# Audio.net
KiCad netlist of a schematic drawn in Altium Designer
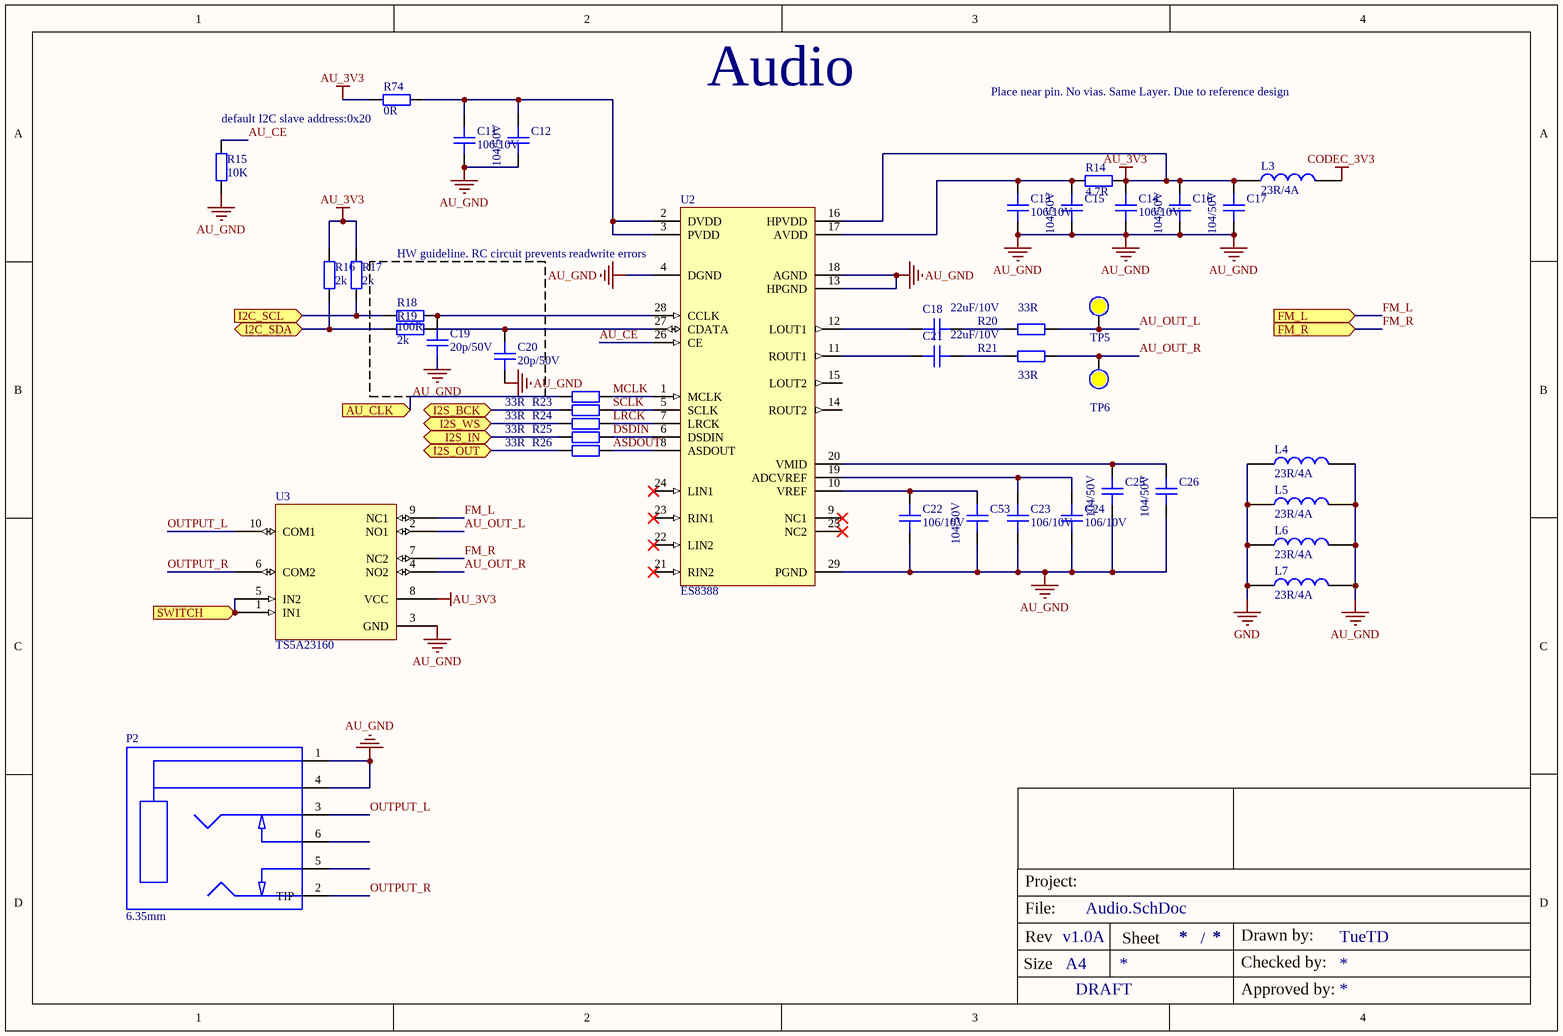
[diagram p0: Audio.SchDoc]

(export (version "E")
  (design (tool "Eeschema 10.0.6"))
  (components
    (comp (ref "C11")
      (value "106/10V")
      (footprint "CAPC-0603 (1608)")
      (description "CAP CER 10uF 10% 10V X5R 0603")
      (fields (field (name "MPN") "CL10A106KP8NNNC"))
      (libsource (lib "lib") (part "CL10A106KP8NNNC"))
    )
    (comp (ref "C12")
      (value "104/50V")
      (footprint "CAPC-0603 (1608)")
      (description "CAP CER 0.1uF 50V 10% X7R 0603")
      (fields (field (name "MPN") "C0603C104K5RACTU"))
      (libsource (lib "lib") (part "C0603C104K5RACTU"))
    )
    (comp (ref "C13")
      (value "106/10V")
      (footprint "CAPC-0603 (1608)")
      (description "CAP CER 10uF 10% 10V X5R 0603")
      (fields (field (name "MPN") "CL10A106KP8NNNC"))
      (libsource (lib "lib") (part "CL10A106KP8NNNC"))
    )
    (comp (ref "C14")
      (value "106/10V")
      (footprint "CAPC-0603 (1608)")
      (description "CAP CER 10uF 10% 10V X5R 0603")
      (fields (field (name "MPN") "CL10A106KP8NNNC"))
      (libsource (lib "lib") (part "CL10A106KP8NNNC"))
    )
    (comp (ref "C15")
      (value "104/50V")
      (footprint "CAPC-0603 (1608)")
      (description "CAP CER 0.1uF 50V 10% X7R 0603")
      (fields (field (name "MPN") "C0603C104K5RACTU"))
      (libsource (lib "lib") (part "C0603C104K5RACTU"))
    )
    (comp (ref "C16")
      (value "104/50V")
      (footprint "CAPC-0603 (1608)")
      (description "CAP CER 0.1uF 50V 10% X7R 0603")
      (fields (field (name "MPN") "C0603C104K5RACTU"))
      (libsource (lib "lib") (part "C0603C104K5RACTU"))
    )
    (comp (ref "C17")
      (value "104/50V")
      (footprint "CAPC-0603 (1608)")
      (description "CAP CER 0.1uF 50V 10% X7R 0603")
      (fields (field (name "MPN") "C0603C104K5RACTU"))
      (libsource (lib "lib") (part "C0603C104K5RACTU"))
    )
    (comp (ref "C18")
      (value "22uF/10V")
      (footprint "CAPC-0603 (1608)")
      (description "CAP CER 22UF 10V X5R 0603")
      (fields (field (name "MPN") "CL10A226MPCNUBE"))
      (libsource (lib "lib") (part "CL10A226MPCNUBE"))
    )
    (comp (ref "C19")
      (value "20p/50V")
      (footprint "CAPC-0603 (1608)")
      (description "CAP CER 20pF 5% 50V C0G/NP0 0603")
      (fields (field (name "MPN") "CL10C200JB8NNNC"))
      (libsource (lib "lib") (part "CL10C200JB8NNNC"))
    )
    (comp (ref "C20")
      (value "20p/50V")
      (footprint "CAPC-0603 (1608)")
      (description "CAP CER 20pF 5% 50V C0G/NP0 0603")
      (fields (field (name "MPN") "CL10C200JB8NNNC"))
      (libsource (lib "lib") (part "CL10C200JB8NNNC"))
    )
    (comp (ref "C21")
      (value "22uF/10V")
      (footprint "CAPC-0603 (1608)")
      (description "CAP CER 22UF 10V X5R 0603")
      (fields (field (name "MPN") "CL10A226MPCNUBE"))
      (libsource (lib "lib") (part "CL10A226MPCNUBE"))
    )
    (comp (ref "C22")
      (value "106/10V")
      (footprint "CAPC-0603 (1608)")
      (description "CAP CER 10uF 10% 10V X5R 0603")
      (fields (field (name "MPN") "CL10A106KP8NNNC"))
      (libsource (lib "lib") (part "CL10A106KP8NNNC"))
    )
    (comp (ref "C23")
      (value "106/10V")
      (footprint "CAPC-0603 (1608)")
      (description "CAP CER 10uF 10% 10V X5R 0603")
      (fields (field (name "MPN") "CL10A106KP8NNNC"))
      (libsource (lib "lib") (part "CL10A106KP8NNNC"))
    )
    (comp (ref "C24")
      (value "106/10V")
      (footprint "CAPC-0603 (1608)")
      (description "CAP CER 10uF 10% 10V X5R 0603")
      (fields (field (name "MPN") "CL10A106KP8NNNC"))
      (libsource (lib "lib") (part "CL10A106KP8NNNC"))
    )
    (comp (ref "C25")
      (value "104/50V")
      (footprint "CAPC-0603 (1608)")
      (description "CAP CER 0.1uF 50V 10% X7R 0603")
      (fields (field (name "MPN") "C0603C104K5RACTU"))
      (libsource (lib "lib") (part "C0603C104K5RACTU"))
    )
    (comp (ref "C26")
      (value "104/50V")
      (footprint "CAPC-0603 (1608)")
      (description "CAP CER 0.1uF 50V 10% X7R 0603")
      (fields (field (name "MPN") "C0603C104K5RACTU"))
      (libsource (lib "lib") (part "C0603C104K5RACTU"))
    )
    (comp (ref "C53")
      (value "104/50V")
      (footprint "CAPC-0603 (1608)")
      (description "CAP CER 0.1uF 50V 10% X7R 0603")
      (fields (field (name "MPN") "C0603C104K5RACTU"))
      (libsource (lib "lib") (part "C0603C104K5RACTU"))
    )
    (comp (ref "L3")
      (value "23R/4A")
      (footprint "IND-0603 (1608)")
      (description "IND-FERRITE BEAD 23 OHM  4A 0603 1LN")
      (fields (field (name "MPN") "FBMJ1608HM230NT"))
      (libsource (lib "lib") (part "FBMJ1608HM230NT"))
    )
    (comp (ref "L4")
      (value "23R/4A")
      (footprint "IND-0603 (1608)")
      (description "IND-FERRITE BEAD 23 OHM  4A 0603 1LN")
      (fields (field (name "MPN") "FBMJ1608HM230NT"))
      (libsource (lib "01.Passives") (part "FBMJ1608HM230NT"))
    )
    (comp (ref "L5")
      (value "23R/4A")
      (footprint "IND-0603 (1608)")
      (description "IND-FERRITE BEAD 23 OHM  4A 0603 1LN")
      (fields (field (name "MPN") "FBMJ1608HM230NT"))
      (libsource (lib "01.Passives") (part "FBMJ1608HM230NT"))
    )
    (comp (ref "L6")
      (value "23R/4A")
      (footprint "IND-0603 (1608)")
      (description "IND-FERRITE BEAD 23 OHM  4A 0603 1LN")
      (fields (field (name "MPN") "FBMJ1608HM230NT"))
      (libsource (lib "01.Passives") (part "FBMJ1608HM230NT"))
    )
    (comp (ref "L7")
      (value "23R/4A")
      (footprint "IND-0603 (1608)")
      (description "IND-FERRITE BEAD 23 OHM  4A 0603 1LN")
      (fields (field (name "MPN") "FBMJ1608HM230NT"))
      (libsource (lib "01.Passives") (part "FBMJ1608HM230NT"))
    )
    (comp (ref "P2")
      (value "6.35mm")
      (footprint "CK-6.35-636A")
      (description "CONN JACK STEREO 1/4\" R/A")
      (fields
        (field (name "MFR") "DONGGUAN YIJIAN ELECTRONICS CO., LTD.")
        (field (name "MPN") "CK-6.35-636A")
      )
      (libsource (lib "lib") (part "CK-6.35-636A"))
    )
    (comp (ref "R14")
      (value "4.7R")
      (footprint "RESC-0603 (1608)")
      (description "RES SMD 4.7 OHM 1% 1/10W 0603")
      (fields (field (name "MPN") "RC0603FR-074R7L"))
      (libsource (lib "lib") (part "RC0603FR-074R7L"))
    )
    (comp (ref "R15")
      (value "10K")
      (footprint "RESC-0603 (1608)")
      (description "RES SMD 10K OHM 1% 1/10W 0603")
      (fields (field (name "MPN") "RC0603FR-0710KL"))
      (libsource (lib "lib") (part "RC0603FR-0710KL"))
    )
    (comp (ref "R16")
      (value "2k")
      (footprint "RESC-0603 (1608)")
      (description "RES SMD 2 KOHM 1% 1/10W 0603")
      (fields (field (name "MPN") "RC0603FR-072KL"))
      (libsource (lib "lib") (part "RC0603FR-072KL"))
    )
    (comp (ref "R17")
      (value "2k")
      (footprint "RESC-0603 (1608)")
      (description "RES SMD 2 KOHM 1% 1/10W 0603")
      (fields (field (name "MPN") "RC0603FR-072KL"))
      (libsource (lib "lib") (part "RC0603FR-072KL"))
    )
    (comp (ref "R18")
      (value "100R")
      (footprint "RESC-0603 (1608)")
      (description "RES SMD 100 OHM 1% 1/10W 0603")
      (fields (field (name "MPN") "RC0603FR-07100RL"))
      (libsource (lib "lib") (part "RC0603FR-07100RL"))
    )
    (comp (ref "R19")
      (value "2k")
      (footprint "RESC-0603 (1608)")
      (description "RES SMD 2 KOHM 1% 1/10W 0603")
      (fields (field (name "MPN") "RC0603FR-072KL"))
      (libsource (lib "") (part "RC0603FR-072KL_1"))
    )
    (comp (ref "R20")
      (value "33R")
      (footprint "RESC-0603 (1608)")
      (description "RES SMD 33 OHM 1% 1/10W 0603")
      (fields (field (name "MPN") "RC0603FR-0733RL") (field (name "MFR") "Yageo"))
      (libsource (lib "lib") (part "RC0603FR-0733RL"))
    )
    (comp (ref "R21")
      (value "33R")
      (footprint "RESC-0603 (1608)")
      (description "RES SMD 33 OHM 1% 1/10W 0603")
      (fields (field (name "MPN") "RC0603FR-0733RL") (field (name "MFR") "Yageo"))
      (libsource (lib "lib") (part "RC0603FR-0733RL"))
    )
    (comp (ref "R22")
      (value "33R")
      (footprint "RESC-0603 (1608)")
      (description "RES SMD 33 OHM 1% 1/10W 0603")
      (fields (field (name "MPN") "RC0603FR-0733RL") (field (name "MFR") "Yageo"))
      (libsource (lib "lib") (part "RC0603FR-0733RL"))
    )
    (comp (ref "R23")
      (value "33R")
      (footprint "RESC-0603 (1608)")
      (description "RES SMD 33 OHM 1% 1/10W 0603")
      (fields (field (name "MPN") "RC0603FR-0733RL") (field (name "MFR") "Yageo"))
      (libsource (lib "lib") (part "RC0603FR-0733RL"))
    )
    (comp (ref "R24")
      (value "33R")
      (footprint "RESC-0603 (1608)")
      (description "RES SMD 33 OHM 1% 1/10W 0603")
      (fields (field (name "MPN") "RC0603FR-0733RL") (field (name "MFR") "Yageo"))
      (libsource (lib "lib") (part "RC0603FR-0733RL"))
    )
    (comp (ref "R25")
      (value "33R")
      (footprint "RESC-0603 (1608)")
      (description "RES SMD 33 OHM 1% 1/10W 0603")
      (fields (field (name "MPN") "RC0603FR-0733RL") (field (name "MFR") "Yageo"))
      (libsource (lib "lib") (part "RC0603FR-0733RL"))
    )
    (comp (ref "R26")
      (value "33R")
      (footprint "RESC-0603 (1608)")
      (description "RES SMD 33 OHM 1% 1/10W 0603")
      (fields (field (name "MPN") "RC0603FR-0733RL") (field (name "MFR") "Yageo"))
      (libsource (lib "lib") (part "RC0603FR-0733RL"))
    )
    (comp (ref "R74")
      (value "0R")
      (footprint "RESC-0603 (1608)")
      (description "RES SMD 0.0OHM JUMPER 1/10W 0603")
      (fields (field (name "MPN") "RC0603FR-070RL"))
      (libsource (lib "lib") (part "RC0603FR-070RL"))
    )
    (comp (ref "TP5")
      (value "~")
      (footprint "Test Point 1.5 MM")
      (description "Test Point")
      (libsource (lib "lib") (part "Test Point"))
    )
    (comp (ref "TP6")
      (value "~")
      (footprint "Test Point 1.5 MM")
      (description "Test Point")
      (libsource (lib "") (part "Test Point_1"))
    )
    (comp (ref "U2")
      (value "ES8388")
      (footprint "QFN28 - ES8388")
      (description "The Audio Codec Chip, is a low power stereo audio codec")
      (fields (field (name "MFR") "Everest-Semi"))
      (libsource (lib "lib") (part "ES8388"))
    )
    (comp (ref "U3")
      (value "TS5A23160")
      (footprint "TSSOP50P490X110-10N")
      (description "IC SWITCH SPDT DUAL 10VSSOP")
      (fields (field (name "MPN") "TS5A23160DGSR") (field (name "MFR") "Texas Instruments"))
      (libsource (lib "lib") (part "TS5A23160DGSR"))
    )
  )
  (nets
    (net (code "1") (name "/ASDOUT") (class "Default")
      (node (ref "R26") (pin "2") (pinfunction "2_2") (pintype "passive"))
      (node (ref "U2") (pin "8") (pinfunction "ASDOUT_8") (pintype "passive"))
    )
    (net (code "2") (name "/AU_CE") (class "Default")
      (node (ref "R15") (pin "2") (pinfunction "2_2") (pintype "passive"))
      (node (ref "U2") (pin "26") (pinfunction "CE_26") (pintype "input"))
    )
    (net (code "3") (name "/AU_CLK") (class "Default")
      (node (ref "R22") (pin "1") (pinfunction "1_1") (pintype "passive"))
    )
    (net (code "4") (name "/AU_OUT_L") (class "Default")
      (node (ref "R20") (pin "2") (pinfunction "2_2") (pintype "passive"))
      (node (ref "TP5") (pin "0") (pinfunction "0_0") (pintype "passive"))
      (node (ref "U3") (pin "2") (pinfunction "NO1_2") (pintype "bidirectional"))
    )
    (net (code "5") (name "/AU_OUT_R") (class "Default")
      (node (ref "R21") (pin "2") (pinfunction "2_2") (pintype "passive"))
      (node (ref "TP6") (pin "0") (pinfunction "0_0") (pintype "passive"))
      (node (ref "U3") (pin "4") (pinfunction "NO2_4") (pintype "bidirectional"))
    )
    (net (code "6") (name "/DSDIN") (class "Default")
      (node (ref "R25") (pin "2") (pinfunction "2_2") (pintype "passive"))
      (node (ref "U2") (pin "6") (pinfunction "DSDIN_6") (pintype "passive"))
    )
    (net (code "7") (name "/FM_L") (class "Default")
      (node (ref "U3") (pin "9") (pinfunction "NC1_9") (pintype "bidirectional"))
    )
    (net (code "8") (name "/FM_R") (class "Default")
      (node (ref "U3") (pin "7") (pinfunction "NC2_7") (pintype "bidirectional"))
    )
    (net (code "9") (name "/I2C_SCL") (class "Default")
      (node (ref "R17") (pin "1") (pinfunction "1_1") (pintype "passive"))
      (node (ref "R18") (pin "1") (pinfunction "1_1") (pintype "passive"))
    )
    (net (code "10") (name "/I2C_SDA") (class "Default")
      (node (ref "R16") (pin "1") (pinfunction "1_1") (pintype "passive"))
      (node (ref "R19") (pin "1") (pinfunction "1_1") (pintype "passive"))
    )
    (net (code "11") (name "/I2S_BCK") (class "Default")
      (node (ref "R23") (pin "1") (pinfunction "1_1") (pintype "passive"))
    )
    (net (code "12") (name "/I2S_IN") (class "Default")
      (node (ref "R25") (pin "1") (pinfunction "1_1") (pintype "passive"))
    )
    (net (code "13") (name "/I2S_OUT") (class "Default")
      (node (ref "R26") (pin "1") (pinfunction "1_1") (pintype "passive"))
    )
    (net (code "14") (name "/I2S_WS") (class "Default")
      (node (ref "R24") (pin "1") (pinfunction "1_1") (pintype "passive"))
    )
    (net (code "15") (name "/LRCK") (class "Default")
      (node (ref "R24") (pin "2") (pinfunction "2_2") (pintype "passive"))
      (node (ref "U2") (pin "7") (pinfunction "LRCK_7") (pintype "passive"))
    )
    (net (code "16") (name "/MCLK") (class "Default")
      (node (ref "R22") (pin "2") (pinfunction "2_2") (pintype "passive"))
      (node (ref "U2") (pin "1") (pinfunction "MCLK_1") (pintype "input"))
    )
    (net (code "17") (name "/OUTPUT_L") (class "Default")
      (node (ref "P2") (pin "3") (pinfunction "RING_3") (pintype "passive"))
      (node (ref "U3") (pin "10") (pinfunction "COM1_10") (pintype "bidirectional"))
    )
    (net (code "18") (name "/OUTPUT_R") (class "Default")
      (node (ref "P2") (pin "2") (pinfunction "TIP_2") (pintype "passive"))
      (node (ref "U3") (pin "6") (pinfunction "COM2_6") (pintype "bidirectional"))
    )
    (net (code "19") (name "/SCLK") (class "Default")
      (node (ref "R23") (pin "2") (pinfunction "2_2") (pintype "passive"))
      (node (ref "U2") (pin "5") (pinfunction "SCLK_5") (pintype "passive"))
    )
    (net (code "20") (name "/SWITCH") (class "Default")
      (node (ref "U3") (pin "1") (pinfunction "IN1_1") (pintype "input"))
      (node (ref "U3") (pin "5") (pinfunction "IN2_5") (pintype "input"))
    )
    (net (code "21") (name "AU_3V3") (class "Default")
      (node (ref "C14") (pin "2") (pinfunction "2_2") (pintype "passive"))
      (node (ref "C16") (pin "2") (pinfunction "2_2") (pintype "passive"))
      (node (ref "C17") (pin "2") (pinfunction "2_2") (pintype "passive"))
      (node (ref "L3") (pin "1") (pinfunction "1_1") (pintype "passive"))
      (node (ref "R14") (pin "2") (pinfunction "2_2") (pintype "passive"))
      (node (ref "R16") (pin "2") (pinfunction "2_2") (pintype "passive"))
      (node (ref "R17") (pin "2") (pinfunction "2_2") (pintype "passive"))
      (node (ref "R74") (pin "1") (pinfunction "1_1") (pintype "passive"))
      (node (ref "U2") (pin "16") (pinfunction "HPVDD_16") (pintype "power_in"))
      (node (ref "U3") (pin "8") (pinfunction "VCC_8") (pintype "power_in"))
    )
    (net (code "22") (name "AU_GND") (class "Default")
      (node (ref "C11") (pin "1") (pinfunction "1_1") (pintype "passive"))
      (node (ref "C12") (pin "1") (pinfunction "1_1") (pintype "passive"))
      (node (ref "C13") (pin "1") (pinfunction "1_1") (pintype "passive"))
      (node (ref "C14") (pin "1") (pinfunction "1_1") (pintype "passive"))
      (node (ref "C15") (pin "1") (pinfunction "1_1") (pintype "passive"))
      (node (ref "C16") (pin "1") (pinfunction "1_1") (pintype "passive"))
      (node (ref "C17") (pin "1") (pinfunction "1_1") (pintype "passive"))
      (node (ref "C19") (pin "1") (pinfunction "1_1") (pintype "passive"))
      (node (ref "C20") (pin "1") (pinfunction "1_1") (pintype "passive"))
      (node (ref "C22") (pin "1") (pinfunction "1_1") (pintype "passive"))
      (node (ref "C23") (pin "1") (pinfunction "1_1") (pintype "passive"))
      (node (ref "C24") (pin "1") (pinfunction "1_1") (pintype "passive"))
      (node (ref "C25") (pin "1") (pinfunction "1_1") (pintype "passive"))
      (node (ref "C26") (pin "1") (pinfunction "1_1") (pintype "passive"))
      (node (ref "C53") (pin "1") (pinfunction "1_1") (pintype "passive"))
      (node (ref "L4") (pin "2") (pinfunction "2_2") (pintype "passive"))
      (node (ref "L5") (pin "2") (pinfunction "2_2") (pintype "passive"))
      (node (ref "L6") (pin "2") (pinfunction "2_2") (pintype "passive"))
      (node (ref "L7") (pin "2") (pinfunction "2_2") (pintype "passive"))
      (node (ref "P2") (pin "1") (pinfunction "SLEEVE_1") (pintype "passive"))
      (node (ref "P2") (pin "4") (pinfunction "SLEEVE_4") (pintype "passive"))
      (node (ref "R15") (pin "1") (pinfunction "1_1") (pintype "passive"))
      (node (ref "U2") (pin "13") (pinfunction "HPGND_13") (pintype "power_in"))
      (node (ref "U2") (pin "18") (pinfunction "AGND_18") (pintype "power_in"))
      (node (ref "U2") (pin "29") (pinfunction "PGND_29") (pintype "power_in"))
      (node (ref "U2") (pin "4") (pinfunction "DGND_4") (pintype "power_in"))
      (node (ref "U3") (pin "3") (pinfunction "GND_3") (pintype "power_in"))
    )
    (net (code "23") (name "CODEC_3V3") (class "Default")
      (node (ref "L3") (pin "2") (pinfunction "2_2") (pintype "passive"))
    )
    (net (code "24") (name "GND") (class "Default")
      (node (ref "L4") (pin "1") (pinfunction "1_1") (pintype "passive"))
      (node (ref "L5") (pin "1") (pinfunction "1_1") (pintype "passive"))
      (node (ref "L6") (pin "1") (pinfunction "1_1") (pintype "passive"))
      (node (ref "L7") (pin "1") (pinfunction "1_1") (pintype "passive"))
    )
    (net (code "25") (name "Net-(C18-Pad1)") (class "Default")
      (node (ref "C18") (pin "1") (pinfunction "1_1") (pintype "passive"))
      (node (ref "R20") (pin "1") (pinfunction "1_1") (pintype "passive"))
    )
    (net (code "26") (name "Net-(C21-Pad1)") (class "Default")
      (node (ref "C21") (pin "1") (pinfunction "1_1") (pintype "passive"))
      (node (ref "R21") (pin "1") (pinfunction "1_1") (pintype "passive"))
    )
    (net (code "27") (name "Net-(U2-ADCVREF)") (class "Default")
      (node (ref "C23") (pin "2") (pinfunction "2_2") (pintype "passive"))
      (node (ref "C24") (pin "2") (pinfunction "2_2") (pintype "passive"))
      (node (ref "U2") (pin "19") (pinfunction "ADCVREF_19") (pintype "passive"))
    )
    (net (code "28") (name "Net-(U2-AVDD)") (class "Default")
      (node (ref "C13") (pin "2") (pinfunction "2_2") (pintype "passive"))
      (node (ref "C15") (pin "2") (pinfunction "2_2") (pintype "passive"))
      (node (ref "R14") (pin "1") (pinfunction "1_1") (pintype "passive"))
      (node (ref "U2") (pin "17") (pinfunction "AVDD_17") (pintype "power_in"))
    )
    (net (code "29") (name "Net-(U2-CCLK)") (class "Default")
      (node (ref "C19") (pin "2") (pinfunction "2_2") (pintype "passive"))
      (node (ref "R18") (pin "2") (pinfunction "2_2") (pintype "passive"))
      (node (ref "U2") (pin "28") (pinfunction "CCLK_28") (pintype "input"))
    )
    (net (code "30") (name "Net-(U2-CDATA)") (class "Default")
      (node (ref "C20") (pin "2") (pinfunction "2_2") (pintype "passive"))
      (node (ref "R19") (pin "2") (pinfunction "2_2") (pintype "passive"))
      (node (ref "U2") (pin "27") (pinfunction "CDATA_27") (pintype "bidirectional"))
    )
    (net (code "31") (name "Net-(U2-DVDD)") (class "Default")
      (node (ref "C11") (pin "2") (pinfunction "2_2") (pintype "passive"))
      (node (ref "C12") (pin "2") (pinfunction "2_2") (pintype "passive"))
      (node (ref "R74") (pin "2") (pinfunction "2_2") (pintype "passive"))
      (node (ref "U2") (pin "2") (pinfunction "DVDD_2") (pintype "power_in"))
      (node (ref "U2") (pin "3") (pinfunction "PVDD_3") (pintype "power_in"))
    )
    (net (code "32") (name "Net-(U2-LOUT1)") (class "Default")
      (node (ref "C18") (pin "2") (pinfunction "2_2") (pintype "passive"))
      (node (ref "U2") (pin "12") (pinfunction "LOUT1_12") (pintype "output"))
    )
    (net (code "33") (name "Net-(U2-ROUT1)") (class "Default")
      (node (ref "C21") (pin "2") (pinfunction "2_2") (pintype "passive"))
      (node (ref "U2") (pin "11") (pinfunction "ROUT1_11") (pintype "output"))
    )
    (net (code "34") (name "Net-(U2-VMID)") (class "Default")
      (node (ref "C25") (pin "2") (pinfunction "2_2") (pintype "passive"))
      (node (ref "C26") (pin "2") (pinfunction "2_2") (pintype "passive"))
      (node (ref "U2") (pin "20") (pinfunction "VMID_20") (pintype "passive"))
    )
    (net (code "35") (name "Net-(U2-VREF)") (class "Default")
      (node (ref "C22") (pin "2") (pinfunction "2_2") (pintype "passive"))
      (node (ref "C53") (pin "2") (pinfunction "2_2") (pintype "passive"))
      (node (ref "U2") (pin "10") (pinfunction "VREF_10") (pintype "passive"))
    )
    (net (code "36") (name "unconnected-(P2-RING_SWITCH-Pad6)") (class "Default")
      (node (ref "P2") (pin "6") (pinfunction "RING_SWITCH_6") (pintype "passive"))
    )
    (net (code "37") (name "unconnected-(P2-TIP_SWITCH-Pad5)") (class "Default")
      (node (ref "P2") (pin "5") (pinfunction "TIP_SWITCH_5") (pintype "passive"))
    )
    (net (code "38") (name "unconnected-(U2-LIN1-Pad24)") (class "Default")
      (node (ref "U2") (pin "24") (pinfunction "LIN1_24") (pintype "input+no_connect"))
    )
    (net (code "39") (name "unconnected-(U2-LIN2-Pad22)") (class "Default")
      (node (ref "U2") (pin "22") (pinfunction "LIN2_22") (pintype "input+no_connect"))
    )
    (net (code "40") (name "unconnected-(U2-LOUT2-Pad15)") (class "Default")
      (node (ref "U2") (pin "15") (pinfunction "LOUT2_15") (pintype "output"))
    )
    (net (code "41") (name "unconnected-(U2-NC1-Pad9)") (class "Default")
      (node (ref "U2") (pin "9") (pinfunction "NC1_9") (pintype "passive+no_connect"))
    )
    (net (code "42") (name "unconnected-(U2-NC2-Pad25)") (class "Default")
      (node (ref "U2") (pin "25") (pinfunction "NC2_25") (pintype "passive+no_connect"))
    )
    (net (code "43") (name "unconnected-(U2-RIN1-Pad23)") (class "Default")
      (node (ref "U2") (pin "23") (pinfunction "RIN1_23") (pintype "input+no_connect"))
    )
    (net (code "44") (name "unconnected-(U2-RIN2-Pad21)") (class "Default")
      (node (ref "U2") (pin "21") (pinfunction "RIN2_21") (pintype "input+no_connect"))
    )
    (net (code "45") (name "unconnected-(U2-ROUT2-Pad14)") (class "Default")
      (node (ref "U2") (pin "14") (pinfunction "ROUT2_14") (pintype "output"))
    )
  )
)
